# Stick_LPC.net
KiCad netlist of a schematic drawn in Altium Designer
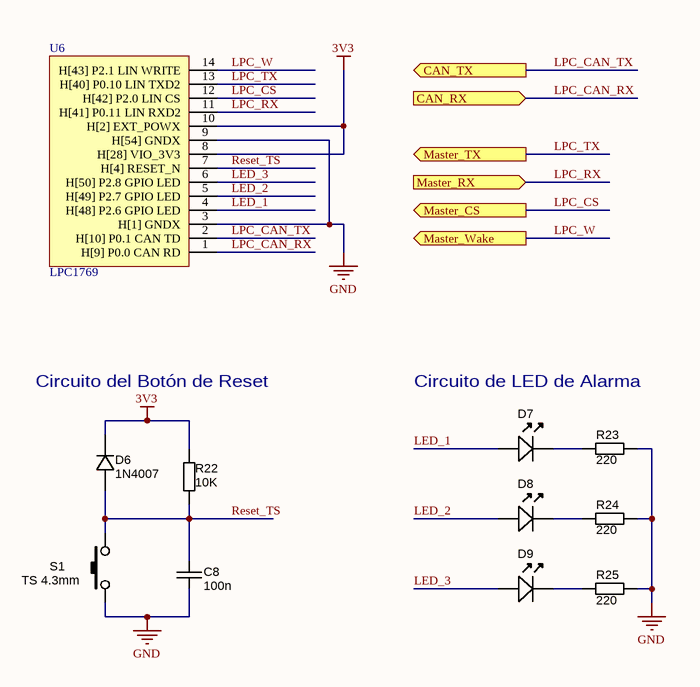
[diagram p0: Stick_LPC.SchDoc]

(export (version "E")
  (design (tool "Eeschema 10.0.6"))
  (components
    (comp (ref "C8")
      (value "100n")
      (footprint "CAPC1608X90N")
      (description "Capacitor SMD Cer 100nF 10% 50V X7R 0603")
      (fields (field (name "TOLERANCE") "±10%"))
      (libsource (lib "PBL - Capacitors") (part "CAPC_47n_0603_X7R_50V_10%"))
    )
    (comp (ref "D6")
      (value "1N4007")
      (footprint "DO-214AC")
      (description "Diode 1N4007 SMD DO-214AC 100V 1.5A SMA")
      (fields (field (name "MANUFACTURER PART NUMBER 1") "1N4007"))
      (libsource (lib "PBL - Diodes") (part "DIODE_100V_1.5A_SMA"))
    )
    (comp (ref "D7")
      (value "Green")
      (footprint "LED-0603-GREEN")
      (description "LED 0603 SMD Green 570nm 50mcd 20mA")
      (libsource (lib "PBL - Light Sources") (part "LED_SMD_Green_0603_570nm"))
    )
    (comp (ref "D8")
      (value "Green")
      (footprint "LED-0603-GREEN")
      (description "LED 0603 SMD Green 570nm 50mcd 20mA")
      (libsource (lib "PBL - Light Sources") (part "LED_SMD_Green_0603_570nm"))
    )
    (comp (ref "D9")
      (value "Green")
      (footprint "LED-0603-GREEN")
      (description "LED 0603 SMD Green 570nm 50mcd 20mA")
      (libsource (lib "PBL - Light Sources") (part "LED_SMD_Green_0603_570nm"))
    )
    (comp (ref "R22")
      (value "10K")
      (footprint "RESC1608N_ZERO")
      (description "Resistor SMD 0603 10K 5%")
      (fields (field (name "TOLERANCE") "±5%"))
      (libsource (lib "") (part "RES_0R_0603_1"))
    )
    (comp (ref "R23")
      (value "220")
      (footprint "RESC1608N_ZERO")
      (description "Resistor SMD 0603 220 Ohm 5%")
      (fields (field (name "TOLERANCE") "±5%"))
      (libsource (lib "PBL - Resistors") (part "RES_0R_0603"))
    )
    (comp (ref "R24")
      (value "220")
      (footprint "RESC1608N_ZERO")
      (description "Resistor SMD 0603 220 Ohm 5%")
      (fields (field (name "TOLERANCE") "±5%"))
      (libsource (lib "PBL - Resistors") (part "RES_0R_0603"))
    )
    (comp (ref "R25")
      (value "220")
      (footprint "RESC1608N_ZERO")
      (description "Resistor SMD 0603 220 Ohm 5%")
      (fields (field (name "TOLERANCE") "±5%"))
      (libsource (lib "PBL - Resistors") (part "RES_0R_0603"))
    )
    (comp (ref "S1")
      (value "SW_THT_PB_4.3mm")
      (footprint "TACT-SWITCH-TS1143")
      (description "Switch, tact, 4.3mm stem")
      (fields (field (name "MANUFACTURER PART NUMBER 1") "TS 4.3mm"))
      (libsource (lib "PBL - Switches") (part "SW_THT_PB_4.3mm"))
    )
    (comp (ref "U6")
      (value "LPC1769")
      (footprint "Header_12")
      (description "LPC1769 Pinera 5mm")
      (libsource (lib "Sch_LPC") (part "LPC1769_Pinera"))
    )
  )
  (nets
    (net (code "1") (name "/LED_1") (class "Default")
      (node (ref "D7") (pin "A") (pinfunction "A_A") (pintype "passive"))
      (node (ref "U6") (pin "4") (pinfunction "H[48]_P2.6_GPIO_LED_4") (pintype "passive"))
    )
    (net (code "2") (name "/LED_2") (class "Default")
      (node (ref "D8") (pin "A") (pinfunction "A_A") (pintype "passive"))
      (node (ref "U6") (pin "5") (pinfunction "H[49]_P2.7_GPIO_LED_5") (pintype "passive"))
    )
    (net (code "3") (name "/LED_3") (class "Default")
      (node (ref "D9") (pin "A") (pinfunction "A_A") (pintype "passive"))
      (node (ref "U6") (pin "6") (pinfunction "H[50]_P2.8_GPIO_LED_6") (pintype "passive"))
    )
    (net (code "4") (name "/LPC_CAN_RX") (class "Default")
      (node (ref "U6") (pin "1") (pinfunction "H[9]_P0.0_CAN_RD_1") (pintype "passive"))
    )
    (net (code "5") (name "/LPC_CAN_TX") (class "Default")
      (node (ref "U6") (pin "2") (pinfunction "H[10]_P0.1_CAN_TD_2") (pintype "passive"))
    )
    (net (code "6") (name "/LPC_CS") (class "Default")
      (node (ref "U6") (pin "12") (pinfunction "H[42]_P2.0_LIN_CS_12") (pintype "passive"))
    )
    (net (code "7") (name "/LPC_RX") (class "Default")
      (node (ref "U6") (pin "11") (pinfunction "H[41]_P0.11_LIN_RXD2_11") (pintype "passive"))
    )
    (net (code "8") (name "/LPC_TX") (class "Default")
      (node (ref "U6") (pin "13") (pinfunction "H[40]_P0.10_LIN_TXD2_13") (pintype "passive"))
    )
    (net (code "9") (name "/LPC_W") (class "Default")
      (node (ref "U6") (pin "14") (pinfunction "H[43]_P2.1_LIN_WRITE_14") (pintype "passive"))
    )
    (net (code "10") (name "/Reset_TS") (class "Default")
      (node (ref "C8") (pin "1") (pintype "passive"))
      (node (ref "D6") (pin "A") (pinfunction "A_A") (pintype "passive"))
      (node (ref "R22") (pin "2") (pinfunction "2_2") (pintype "passive"))
      (node (ref "S1") (pin "2") (pintype "passive"))
      (node (ref "U6") (pin "7") (pinfunction "H[4]_RESET_N_7") (pintype "passive"))
    )
    (net (code "11") (name "3V3") (class "Default")
      (node (ref "D6") (pin "K") (pinfunction "K_K") (pintype "passive"))
      (node (ref "R22") (pin "1") (pinfunction "1_1") (pintype "passive"))
      (node (ref "U6") (pin "10") (pinfunction "H[2]_EXT_POWX_10") (pintype "passive"))
      (node (ref "U6") (pin "8") (pinfunction "H[28]_VIO_3V3_8") (pintype "passive"))
    )
    (net (code "12") (name "GND") (class "Default")
      (node (ref "C8") (pin "2") (pintype "passive"))
      (node (ref "R23") (pin "2") (pinfunction "2_2") (pintype "passive"))
      (node (ref "R24") (pin "2") (pinfunction "2_2") (pintype "passive"))
      (node (ref "R25") (pin "2") (pinfunction "2_2") (pintype "passive"))
      (node (ref "S1") (pin "1") (pintype "passive"))
      (node (ref "U6") (pin "3") (pinfunction "H[1]_GNDX_3") (pintype "passive"))
      (node (ref "U6") (pin "9") (pinfunction "H[54]_GNDX_9") (pintype "passive"))
    )
    (net (code "13") (name "Net-(D7-PadK)") (class "Default")
      (node (ref "D7") (pin "K") (pinfunction "K_K") (pintype "passive"))
      (node (ref "R23") (pin "1") (pinfunction "1_1") (pintype "passive"))
    )
    (net (code "14") (name "Net-(D8-PadK)") (class "Default")
      (node (ref "D8") (pin "K") (pinfunction "K_K") (pintype "passive"))
      (node (ref "R24") (pin "1") (pinfunction "1_1") (pintype "passive"))
    )
    (net (code "15") (name "Net-(D9-PadK)") (class "Default")
      (node (ref "D9") (pin "K") (pinfunction "K_K") (pintype "passive"))
      (node (ref "R25") (pin "1") (pinfunction "1_1") (pintype "passive"))
    )
  )
)
